# Analog_Slave.net
KiCad netlist of a schematic drawn in EAGLE
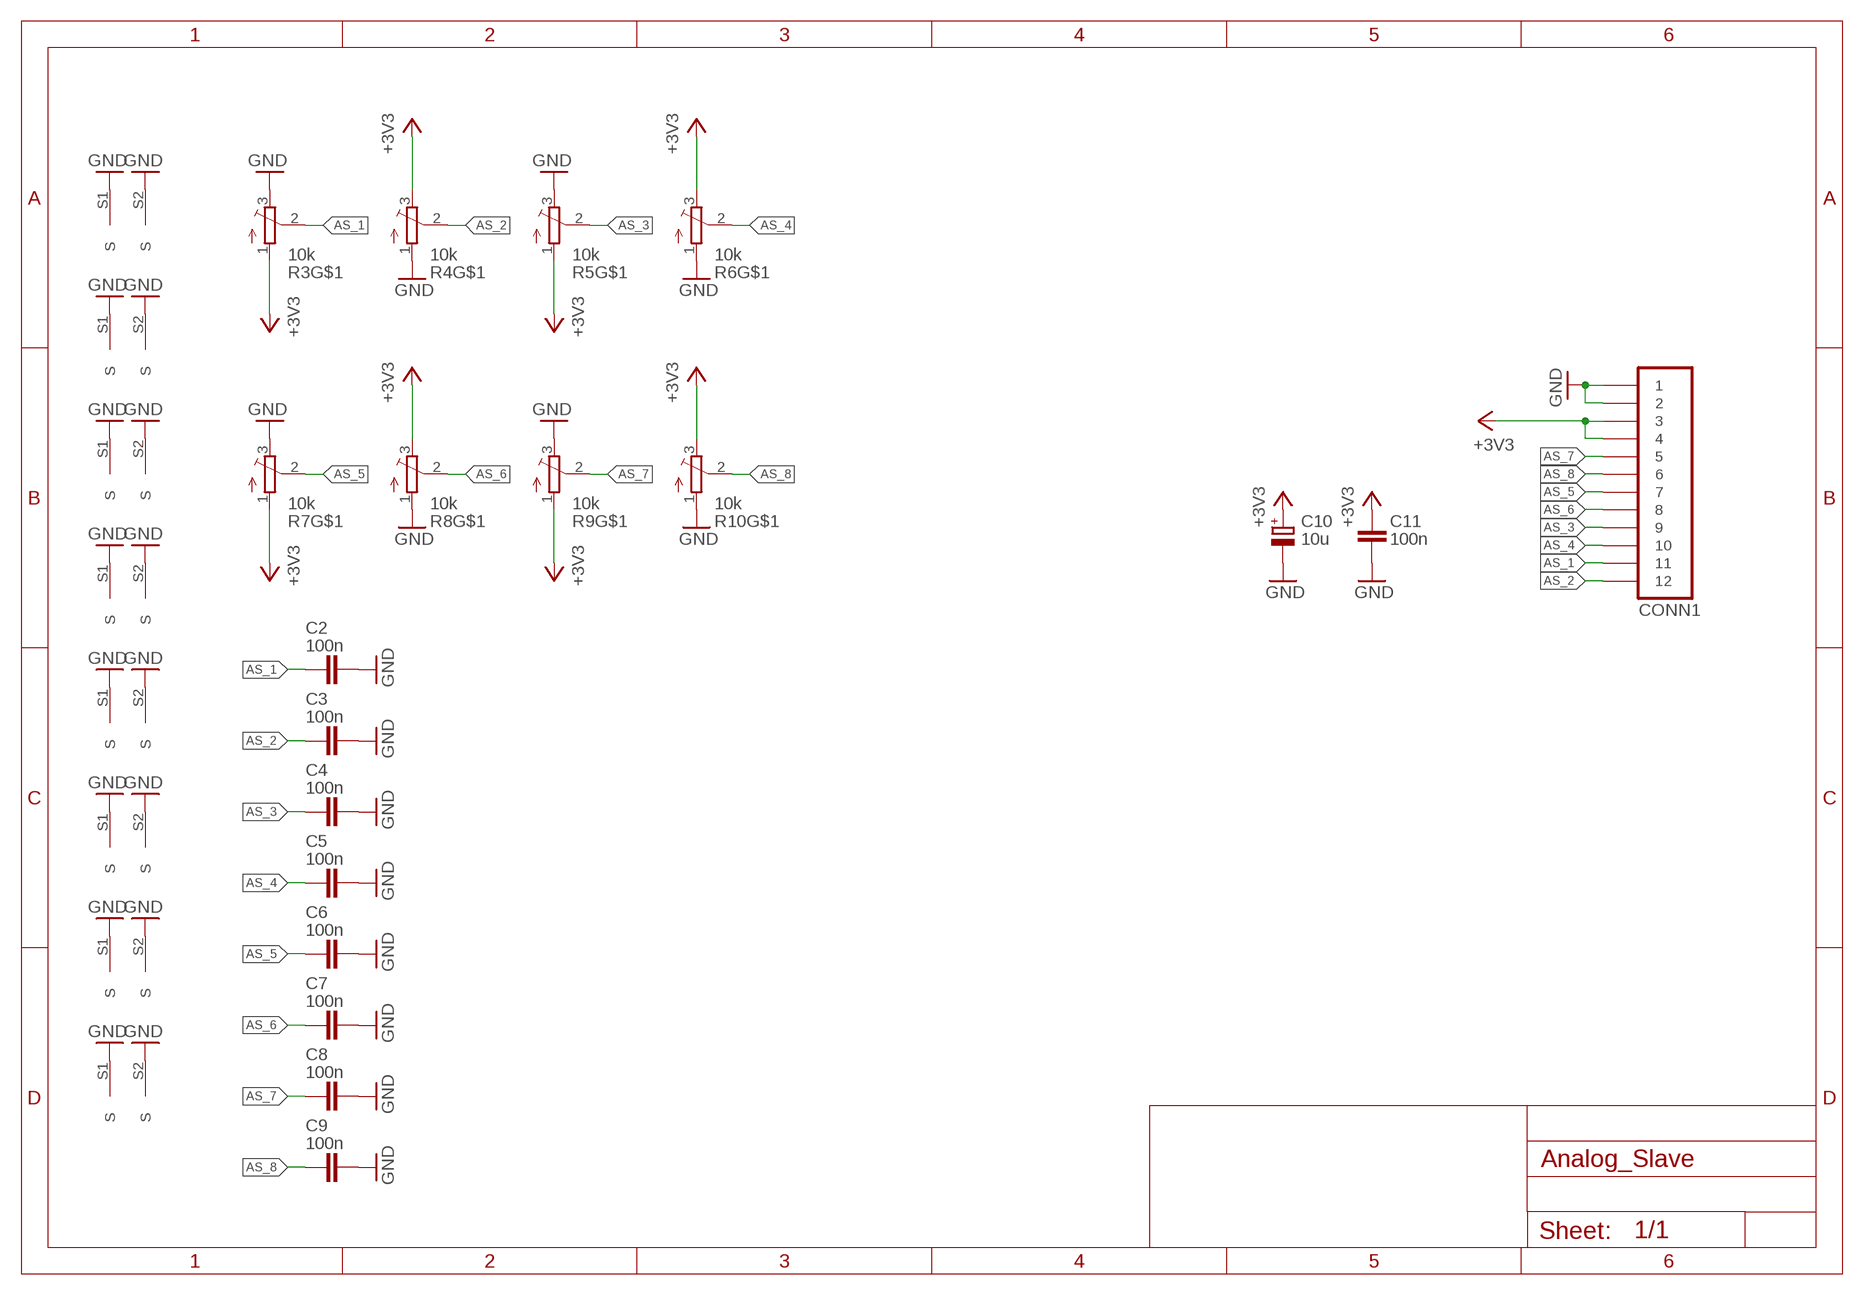
[diagram p0: schematic, sheet 1]

(export (version "E")
  (design (tool "Eeschema 10.0.6"))
  (components
    (comp (ref "C2")
      (value "100n")
      (footprint "eagle-import:C0805")
      (libsource (lib "eagle-import") (part "CAPACITOR-0805"))
    )
    (comp (ref "C3")
      (value "100n")
      (footprint "eagle-import:C0805")
      (libsource (lib "eagle-import") (part "CAPACITOR-0805"))
    )
    (comp (ref "C4")
      (value "100n")
      (footprint "eagle-import:C0805")
      (libsource (lib "eagle-import") (part "CAPACITOR-0805"))
    )
    (comp (ref "C5")
      (value "100n")
      (footprint "eagle-import:C0805")
      (libsource (lib "eagle-import") (part "CAPACITOR-0805"))
    )
    (comp (ref "C6")
      (value "100n")
      (footprint "eagle-import:C0805")
      (libsource (lib "eagle-import") (part "CAPACITOR-0805"))
    )
    (comp (ref "C7")
      (value "100n")
      (footprint "eagle-import:C0805")
      (libsource (lib "eagle-import") (part "CAPACITOR-0805"))
    )
    (comp (ref "C8")
      (value "100n")
      (footprint "eagle-import:C0805")
      (libsource (lib "eagle-import") (part "CAPACITOR-0805"))
    )
    (comp (ref "C9")
      (value "100n")
      (footprint "eagle-import:C0805")
      (libsource (lib "eagle-import") (part "CAPACITOR-0805"))
    )
    (comp (ref "C10")
      (value "10u")
      (footprint "eagle-import:153CLV-0405")
      (fields (field (name "MANUFACTURER") "Multicomp") (field (name "MPN") "MCVVT016M100CA1L"))
      (libsource (lib "eagle-import") (part "ELECTROLYTIC_CAPACITOR-CLV-040516V"))
    )
    (comp (ref "C11")
      (value "100n")
      (footprint "eagle-import:C0805")
      (libsource (lib "eagle-import") (part "CAPACITOR-0805"))
    )
    (comp (ref "CONN1")
      (value "PINHD-2X06-IDC-2.54-V")
      (footprint "eagle-import:IDC-12P-2.54")
      (libsource (lib "eagle-import") (part "PINHD-2X06-IDC-2.54-V"))
    )
    (comp (ref "R3")
      (value "10k")
      (footprint "eagle-import:PTV09A-4025F-B103")
      (libsource (lib "eagle-import") (part "PTV09A-4025F-B103"))
    )
    (comp (ref "R4")
      (value "10k")
      (footprint "eagle-import:PTV09A-4025F-B103")
      (libsource (lib "eagle-import") (part "PTV09A-4025F-B103"))
    )
    (comp (ref "R5")
      (value "10k")
      (footprint "eagle-import:PTV09A-4025F-B103")
      (libsource (lib "eagle-import") (part "PTV09A-4025F-B103"))
    )
    (comp (ref "R6")
      (value "10k")
      (footprint "eagle-import:PTV09A-4025F-B103")
      (libsource (lib "eagle-import") (part "PTV09A-4025F-B103"))
    )
    (comp (ref "R7")
      (value "10k")
      (footprint "eagle-import:PTV09A-4025F-B103")
      (libsource (lib "eagle-import") (part "PTV09A-4025F-B103"))
    )
    (comp (ref "R8")
      (value "10k")
      (footprint "eagle-import:PTV09A-4025F-B103")
      (libsource (lib "eagle-import") (part "PTV09A-4025F-B103"))
    )
    (comp (ref "R9")
      (value "10k")
      (footprint "eagle-import:PTV09A-4025F-B103")
      (libsource (lib "eagle-import") (part "PTV09A-4025F-B103"))
    )
    (comp (ref "R10")
      (value "10k")
      (footprint "eagle-import:PTV09A-4025F-B103")
      (libsource (lib "eagle-import") (part "PTV09A-4025F-B103"))
    )
  )
  (nets
    (net (code "1") (name "+3V3") (class "Default")
      (node (ref "C10") (pin "+") (pinfunction "+_+") (pintype "passive"))
      (node (ref "C11") (pin "1") (pinfunction "1_1") (pintype "passive"))
      (node (ref "CONN1") (pin "3") (pinfunction "3_3") (pintype "passive"))
      (node (ref "CONN1") (pin "4") (pinfunction "4_4") (pintype "passive"))
      (node (ref "R10") (pin "3") (pinfunction "3_3") (pintype "passive"))
      (node (ref "R3") (pin "1") (pinfunction "1_1") (pintype "passive"))
      (node (ref "R4") (pin "3") (pinfunction "3_3") (pintype "passive"))
      (node (ref "R5") (pin "1") (pinfunction "1_1") (pintype "passive"))
      (node (ref "R6") (pin "3") (pinfunction "3_3") (pintype "passive"))
      (node (ref "R7") (pin "1") (pinfunction "1_1") (pintype "passive"))
      (node (ref "R8") (pin "3") (pinfunction "3_3") (pintype "passive"))
      (node (ref "R9") (pin "1") (pinfunction "1_1") (pintype "passive"))
    )
    (net (code "2") (name "AS_1") (class "Default")
      (node (ref "C2") (pin "1") (pinfunction "1_1") (pintype "passive"))
      (node (ref "CONN1") (pin "11") (pinfunction "11_11") (pintype "passive"))
      (node (ref "R3") (pin "2") (pinfunction "2_2") (pintype "passive"))
    )
    (net (code "3") (name "AS_2") (class "Default")
      (node (ref "C3") (pin "1") (pinfunction "1_1") (pintype "passive"))
      (node (ref "CONN1") (pin "12") (pinfunction "12_12") (pintype "passive"))
      (node (ref "R4") (pin "2") (pinfunction "2_2") (pintype "passive"))
    )
    (net (code "4") (name "AS_3") (class "Default")
      (node (ref "C4") (pin "1") (pinfunction "1_1") (pintype "passive"))
      (node (ref "CONN1") (pin "9") (pinfunction "9_9") (pintype "passive"))
      (node (ref "R5") (pin "2") (pinfunction "2_2") (pintype "passive"))
    )
    (net (code "5") (name "AS_4") (class "Default")
      (node (ref "C5") (pin "1") (pinfunction "1_1") (pintype "passive"))
      (node (ref "CONN1") (pin "10") (pinfunction "10_10") (pintype "passive"))
      (node (ref "R6") (pin "2") (pinfunction "2_2") (pintype "passive"))
    )
    (net (code "6") (name "AS_5") (class "Default")
      (node (ref "C6") (pin "1") (pinfunction "1_1") (pintype "passive"))
      (node (ref "CONN1") (pin "7") (pinfunction "7_7") (pintype "passive"))
      (node (ref "R7") (pin "2") (pinfunction "2_2") (pintype "passive"))
    )
    (net (code "7") (name "AS_6") (class "Default")
      (node (ref "C7") (pin "1") (pinfunction "1_1") (pintype "passive"))
      (node (ref "CONN1") (pin "8") (pinfunction "8_8") (pintype "passive"))
      (node (ref "R8") (pin "2") (pinfunction "2_2") (pintype "passive"))
    )
    (net (code "8") (name "AS_7") (class "Default")
      (node (ref "C8") (pin "1") (pinfunction "1_1") (pintype "passive"))
      (node (ref "CONN1") (pin "5") (pinfunction "5_5") (pintype "passive"))
      (node (ref "R9") (pin "2") (pinfunction "2_2") (pintype "passive"))
    )
    (net (code "9") (name "AS_8") (class "Default")
      (node (ref "C9") (pin "1") (pinfunction "1_1") (pintype "passive"))
      (node (ref "CONN1") (pin "6") (pinfunction "6_6") (pintype "passive"))
      (node (ref "R10") (pin "2") (pinfunction "2_2") (pintype "passive"))
    )
    (net (code "10") (name "GND") (class "Default")
      (node (ref "C10") (pin "-") (pinfunction "-_-") (pintype "passive"))
      (node (ref "C11") (pin "2") (pinfunction "2_2") (pintype "passive"))
      (node (ref "C2") (pin "2") (pinfunction "2_2") (pintype "passive"))
      (node (ref "C3") (pin "2") (pinfunction "2_2") (pintype "passive"))
      (node (ref "C4") (pin "2") (pinfunction "2_2") (pintype "passive"))
      (node (ref "C5") (pin "2") (pinfunction "2_2") (pintype "passive"))
      (node (ref "C6") (pin "2") (pinfunction "2_2") (pintype "passive"))
      (node (ref "C7") (pin "2") (pinfunction "2_2") (pintype "passive"))
      (node (ref "C8") (pin "2") (pinfunction "2_2") (pintype "passive"))
      (node (ref "C9") (pin "2") (pinfunction "2_2") (pintype "passive"))
      (node (ref "CONN1") (pin "1") (pinfunction "1_1") (pintype "passive"))
      (node (ref "CONN1") (pin "2") (pinfunction "2_2") (pintype "passive"))
      (node (ref "R10") (pin "1") (pinfunction "1_1") (pintype "passive"))
      (node (ref "R10") (pin "S1") (pinfunction "S_S1") (pintype "passive"))
      (node (ref "R10") (pin "S2") (pinfunction "S_S2") (pintype "passive"))
      (node (ref "R3") (pin "3") (pinfunction "3_3") (pintype "passive"))
      (node (ref "R3") (pin "S1") (pinfunction "S_S1") (pintype "passive"))
      (node (ref "R3") (pin "S2") (pinfunction "S_S2") (pintype "passive"))
      (node (ref "R4") (pin "1") (pinfunction "1_1") (pintype "passive"))
      (node (ref "R4") (pin "S1") (pinfunction "S_S1") (pintype "passive"))
      (node (ref "R4") (pin "S2") (pinfunction "S_S2") (pintype "passive"))
      (node (ref "R5") (pin "3") (pinfunction "3_3") (pintype "passive"))
      (node (ref "R5") (pin "S1") (pinfunction "S_S1") (pintype "passive"))
      (node (ref "R5") (pin "S2") (pinfunction "S_S2") (pintype "passive"))
      (node (ref "R6") (pin "1") (pinfunction "1_1") (pintype "passive"))
      (node (ref "R6") (pin "S1") (pinfunction "S_S1") (pintype "passive"))
      (node (ref "R6") (pin "S2") (pinfunction "S_S2") (pintype "passive"))
      (node (ref "R7") (pin "3") (pinfunction "3_3") (pintype "passive"))
      (node (ref "R7") (pin "S1") (pinfunction "S_S1") (pintype "passive"))
      (node (ref "R7") (pin "S2") (pinfunction "S_S2") (pintype "passive"))
      (node (ref "R8") (pin "1") (pinfunction "1_1") (pintype "passive"))
      (node (ref "R8") (pin "S1") (pinfunction "S_S1") (pintype "passive"))
      (node (ref "R8") (pin "S2") (pinfunction "S_S2") (pintype "passive"))
      (node (ref "R9") (pin "3") (pinfunction "3_3") (pintype "passive"))
      (node (ref "R9") (pin "S1") (pinfunction "S_S1") (pintype "passive"))
      (node (ref "R9") (pin "S2") (pinfunction "S_S2") (pintype "passive"))
    )
  )
)
